# OSSIDevBoard.net
KiCad netlist of a schematic drawn in EAGLE
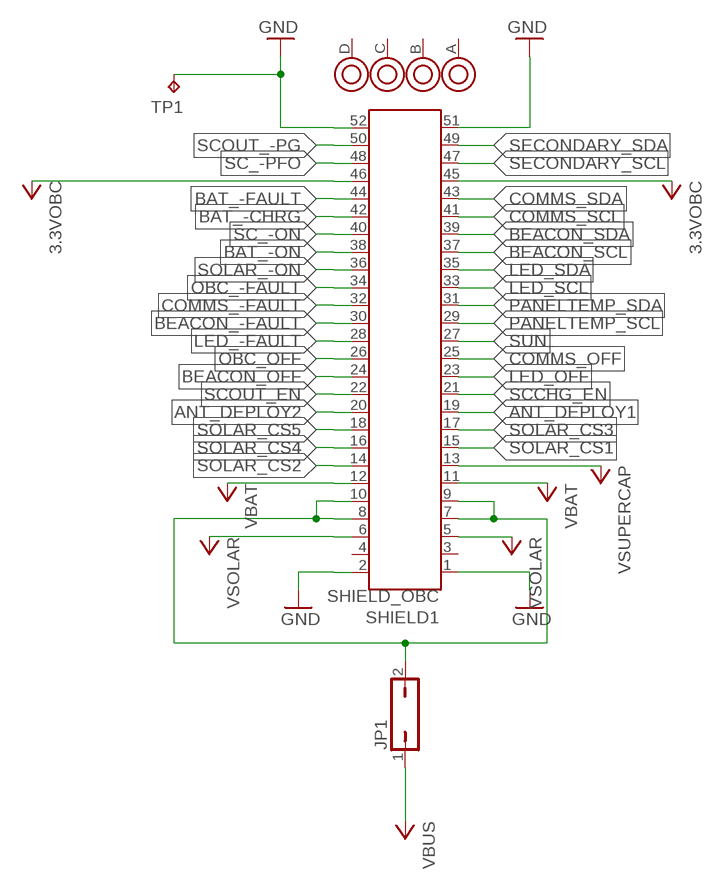
[diagram p0: schematic, sheet 1, part 1 of 2]
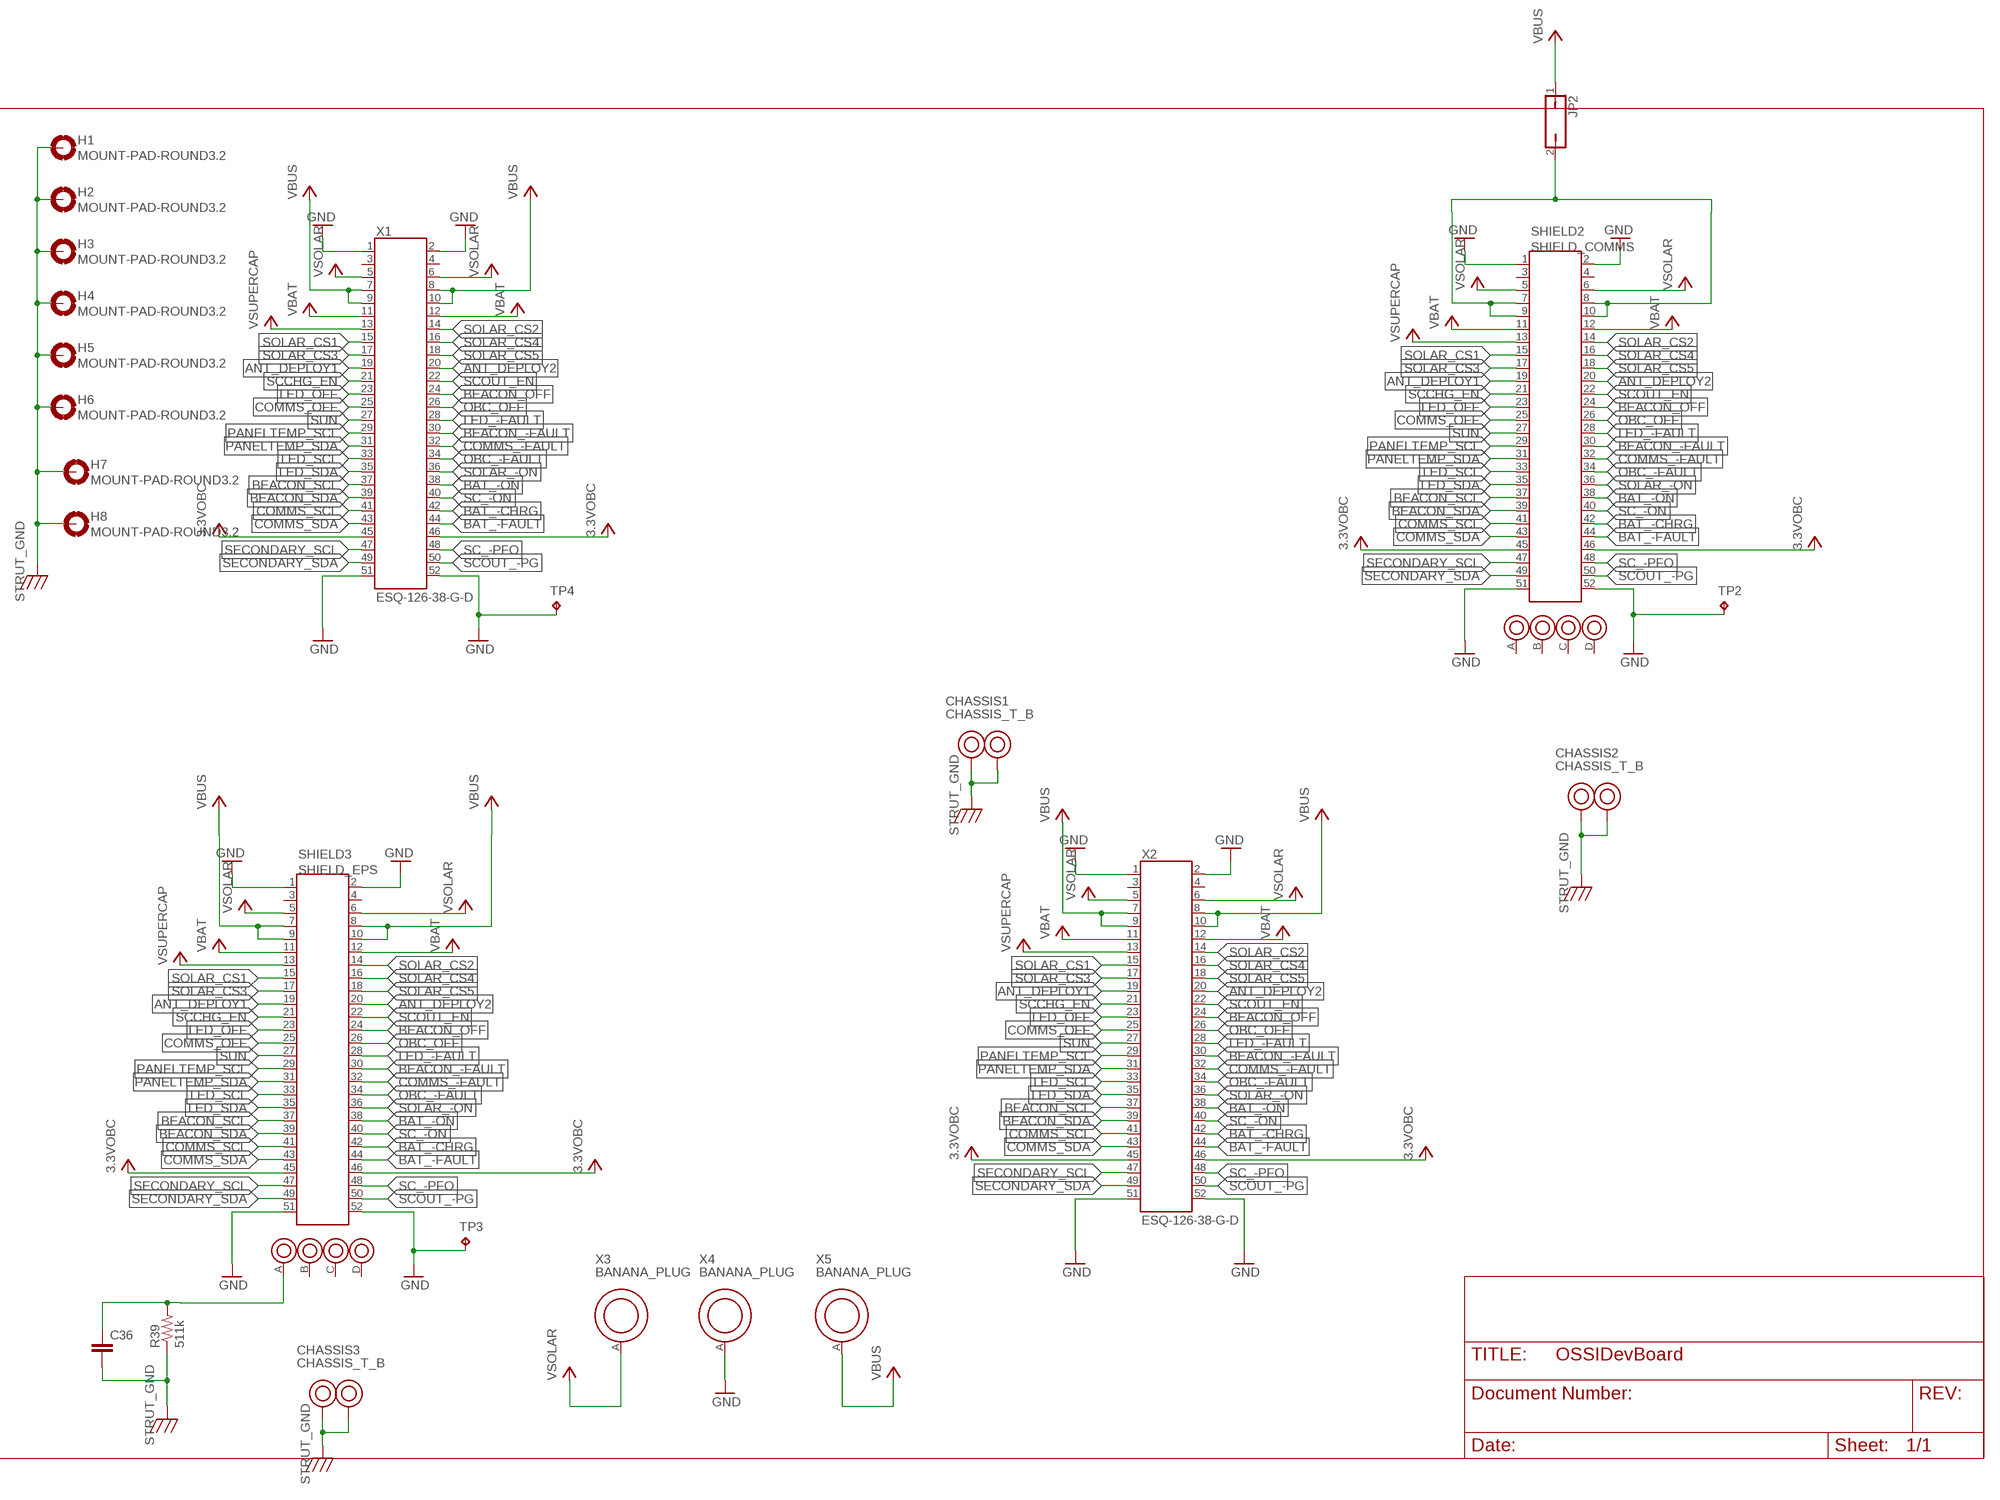
[diagram p1: schematic, sheet 1, part 2 of 2]

(export (version "E")
  (design (tool "Eeschema 10.0.6"))
  (components
    (comp (ref "C36")
      (value "C0805(2012)")
      (footprint "eagle-import:C0805(2012)")
      (libsource (lib "eagle-import") (part "C0805(2012)"))
    )
    (comp (ref "CHASSIS1")
      (value "CHASSIS_T_B")
      (footprint "eagle-import:CHASSIS_T_B")
      (libsource (lib "eagle-import") (part "CHASSIS_T_B"))
    )
    (comp (ref "CHASSIS2")
      (value "CHASSIS_T_B")
      (footprint "eagle-import:CHASSIS_T_B")
      (libsource (lib "eagle-import") (part "CHASSIS_T_B"))
    )
    (comp (ref "CHASSIS3")
      (value "CHASSIS_T_B")
      (footprint "eagle-import:CHASSIS_T_B")
      (libsource (lib "eagle-import") (part "CHASSIS_T_B"))
    )
    (comp (ref "H1")
      (value "MOUNT-PAD-ROUND3.2")
      (footprint "eagle-import:3.2-PAD-ROUND")
      (libsource (lib "eagle-import") (part "MOUNT-PAD-ROUND3.2"))
    )
    (comp (ref "H2")
      (value "MOUNT-PAD-ROUND3.2")
      (footprint "eagle-import:3.2-PAD-ROUND")
      (libsource (lib "eagle-import") (part "MOUNT-PAD-ROUND3.2"))
    )
    (comp (ref "H3")
      (value "MOUNT-PAD-ROUND3.2")
      (footprint "eagle-import:3.2-PAD-ROUND")
      (libsource (lib "eagle-import") (part "MOUNT-PAD-ROUND3.2"))
    )
    (comp (ref "H4")
      (value "MOUNT-PAD-ROUND3.2")
      (footprint "eagle-import:3.2-PAD-ROUND")
      (libsource (lib "eagle-import") (part "MOUNT-PAD-ROUND3.2"))
    )
    (comp (ref "H5")
      (value "MOUNT-PAD-ROUND3.2")
      (footprint "eagle-import:3.2-PAD-ROUND")
      (libsource (lib "eagle-import") (part "MOUNT-PAD-ROUND3.2"))
    )
    (comp (ref "H6")
      (value "MOUNT-PAD-ROUND3.2")
      (footprint "eagle-import:3.2-PAD-ROUND")
      (libsource (lib "eagle-import") (part "MOUNT-PAD-ROUND3.2"))
    )
    (comp (ref "H7")
      (value "MOUNT-PAD-ROUND3.2")
      (footprint "eagle-import:3.2-PAD-ROUND")
      (libsource (lib "eagle-import") (part "MOUNT-PAD-ROUND3.2"))
    )
    (comp (ref "H8")
      (value "MOUNT-PAD-ROUND3.2")
      (footprint "eagle-import:3.2-PAD-ROUND")
      (libsource (lib "eagle-import") (part "MOUNT-PAD-ROUND3.2"))
    )
    (comp (ref "JP1")
      (value "JP1Q")
      (footprint "eagle-import:JP1")
      (libsource (lib "eagle-import") (part "JP1Q"))
    )
    (comp (ref "JP2")
      (value "JP1Q")
      (footprint "eagle-import:JP1")
      (libsource (lib "eagle-import") (part "JP1Q"))
    )
    (comp (ref "R39")
      (value "511k")
      (footprint "eagle-import:R0805(2012)")
      (libsource (lib "eagle-import") (part "R0805(2012)"))
    )
    (comp (ref "SHIELD1")
      (value "SHIELD_OBC")
      (footprint "eagle-import:OBC_SHIELD")
      (libsource (lib "eagle-import") (part "SHIELD_OBC"))
    )
    (comp (ref "SHIELD2")
      (value "SHIELD_COMMS")
      (footprint "eagle-import:COMMS_SHIELD")
      (libsource (lib "eagle-import") (part "SHIELD_COMMS"))
    )
    (comp (ref "SHIELD3")
      (value "SHIELD_EPS")
      (footprint "eagle-import:EPS_SHIELD")
      (libsource (lib "eagle-import") (part "SHIELD_EPS"))
    )
    (comp (ref "TP1")
      (value "TP")
      (footprint "eagle-import:TP-13")
      (libsource (lib "eagle-import") (part "TP"))
    )
    (comp (ref "TP2")
      (value "TP")
      (footprint "eagle-import:TP-13")
      (libsource (lib "eagle-import") (part "TP"))
    )
    (comp (ref "TP3")
      (value "TP")
      (footprint "eagle-import:TP-13")
      (libsource (lib "eagle-import") (part "TP"))
    )
    (comp (ref "TP4")
      (value "TP")
      (footprint "eagle-import:TP-13")
      (libsource (lib "eagle-import") (part "TP"))
    )
    (comp (ref "X1")
      (value "ESQ-126-38-G-D")
      (footprint "eagle-import:ESQ-126-XX-X-D")
      (libsource (lib "eagle-import") (part "ESQ-126-38-G-D"))
    )
    (comp (ref "X2")
      (value "ESQ-126-38-G-D")
      (footprint "eagle-import:ESQ-126-XX-X-D")
      (libsource (lib "eagle-import") (part "ESQ-126-38-G-D"))
    )
    (comp (ref "X3")
      (value "BANANA_PLUG")
      (footprint "eagle-import:BANANA_PLUG")
      (libsource (lib "eagle-import") (part "BANANA_PLUG"))
    )
    (comp (ref "X4")
      (value "BANANA_PLUG")
      (footprint "eagle-import:BANANA_PLUG")
      (libsource (lib "eagle-import") (part "BANANA_PLUG"))
    )
    (comp (ref "X5")
      (value "BANANA_PLUG")
      (footprint "eagle-import:BANANA_PLUG")
      (libsource (lib "eagle-import") (part "BANANA_PLUG"))
    )
  )
  (nets
    (net (code "1") (name "3.3VOBC") (class "Default")
      (node (ref "SHIELD1") (pin "45") (pinfunction "45_45") (pintype "bidirectional"))
      (node (ref "SHIELD1") (pin "46") (pinfunction "46_46") (pintype "bidirectional"))
      (node (ref "SHIELD2") (pin "45") (pinfunction "45_45") (pintype "bidirectional"))
      (node (ref "SHIELD2") (pin "46") (pinfunction "46_46") (pintype "bidirectional"))
      (node (ref "SHIELD3") (pin "45") (pinfunction "45_45") (pintype "bidirectional"))
      (node (ref "SHIELD3") (pin "46") (pinfunction "46_46") (pintype "bidirectional"))
      (node (ref "X1") (pin "45") (pinfunction "45_45") (pintype "bidirectional"))
      (node (ref "X1") (pin "46") (pinfunction "46_46") (pintype "bidirectional"))
      (node (ref "X2") (pin "45") (pinfunction "45_45") (pintype "bidirectional"))
      (node (ref "X2") (pin "46") (pinfunction "46_46") (pintype "bidirectional"))
    )
    (net (code "2") (name "ANT_DEPLOY1") (class "Default")
      (node (ref "SHIELD1") (pin "19") (pinfunction "19_19") (pintype "bidirectional"))
      (node (ref "SHIELD2") (pin "19") (pinfunction "19_19") (pintype "bidirectional"))
      (node (ref "SHIELD3") (pin "19") (pinfunction "19_19") (pintype "bidirectional"))
      (node (ref "X1") (pin "19") (pinfunction "19_19") (pintype "bidirectional"))
      (node (ref "X2") (pin "19") (pinfunction "19_19") (pintype "bidirectional"))
    )
    (net (code "3") (name "ANT_DEPLOY2") (class "Default")
      (node (ref "SHIELD1") (pin "20") (pinfunction "20_20") (pintype "bidirectional"))
      (node (ref "SHIELD2") (pin "20") (pinfunction "20_20") (pintype "bidirectional"))
      (node (ref "SHIELD3") (pin "20") (pinfunction "20_20") (pintype "bidirectional"))
      (node (ref "X1") (pin "20") (pinfunction "20_20") (pintype "bidirectional"))
      (node (ref "X2") (pin "20") (pinfunction "20_20") (pintype "bidirectional"))
    )
    (net (code "4") (name "BAT_-CHRG") (class "Default")
      (node (ref "SHIELD1") (pin "42") (pinfunction "42_42") (pintype "bidirectional"))
      (node (ref "SHIELD2") (pin "42") (pinfunction "42_42") (pintype "bidirectional"))
      (node (ref "SHIELD3") (pin "42") (pinfunction "42_42") (pintype "bidirectional"))
      (node (ref "X1") (pin "42") (pinfunction "42_42") (pintype "bidirectional"))
      (node (ref "X2") (pin "42") (pinfunction "42_42") (pintype "bidirectional"))
    )
    (net (code "5") (name "BAT_-FAULT") (class "Default")
      (node (ref "SHIELD1") (pin "44") (pinfunction "44_44") (pintype "bidirectional"))
      (node (ref "SHIELD2") (pin "44") (pinfunction "44_44") (pintype "bidirectional"))
      (node (ref "SHIELD3") (pin "44") (pinfunction "44_44") (pintype "bidirectional"))
      (node (ref "X1") (pin "44") (pinfunction "44_44") (pintype "bidirectional"))
      (node (ref "X2") (pin "44") (pinfunction "44_44") (pintype "bidirectional"))
    )
    (net (code "6") (name "BAT_-ON") (class "Default")
      (node (ref "SHIELD1") (pin "38") (pinfunction "38_38") (pintype "bidirectional"))
      (node (ref "SHIELD2") (pin "38") (pinfunction "38_38") (pintype "bidirectional"))
      (node (ref "SHIELD3") (pin "38") (pinfunction "38_38") (pintype "bidirectional"))
      (node (ref "X1") (pin "38") (pinfunction "38_38") (pintype "bidirectional"))
      (node (ref "X2") (pin "38") (pinfunction "38_38") (pintype "bidirectional"))
    )
    (net (code "7") (name "BEACON_-FAULT") (class "Default")
      (node (ref "SHIELD1") (pin "30") (pinfunction "30_30") (pintype "bidirectional"))
      (node (ref "SHIELD2") (pin "30") (pinfunction "30_30") (pintype "bidirectional"))
      (node (ref "SHIELD3") (pin "30") (pinfunction "30_30") (pintype "bidirectional"))
      (node (ref "X1") (pin "30") (pinfunction "30_30") (pintype "bidirectional"))
      (node (ref "X2") (pin "30") (pinfunction "30_30") (pintype "bidirectional"))
    )
    (net (code "8") (name "BEACON_OFF") (class "Default")
      (node (ref "SHIELD1") (pin "24") (pinfunction "24_24") (pintype "bidirectional"))
      (node (ref "SHIELD2") (pin "24") (pinfunction "24_24") (pintype "bidirectional"))
      (node (ref "SHIELD3") (pin "24") (pinfunction "24_24") (pintype "bidirectional"))
      (node (ref "X1") (pin "24") (pinfunction "24_24") (pintype "bidirectional"))
      (node (ref "X2") (pin "24") (pinfunction "24_24") (pintype "bidirectional"))
    )
    (net (code "9") (name "BEACON_SCL") (class "Default")
      (node (ref "SHIELD1") (pin "37") (pinfunction "37_37") (pintype "bidirectional"))
      (node (ref "SHIELD2") (pin "37") (pinfunction "37_37") (pintype "bidirectional"))
      (node (ref "SHIELD3") (pin "37") (pinfunction "37_37") (pintype "bidirectional"))
      (node (ref "X1") (pin "37") (pinfunction "37_37") (pintype "bidirectional"))
      (node (ref "X2") (pin "37") (pinfunction "37_37") (pintype "bidirectional"))
    )
    (net (code "10") (name "BEACON_SDA") (class "Default")
      (node (ref "SHIELD1") (pin "39") (pinfunction "39_39") (pintype "bidirectional"))
      (node (ref "SHIELD2") (pin "39") (pinfunction "39_39") (pintype "bidirectional"))
      (node (ref "SHIELD3") (pin "39") (pinfunction "39_39") (pintype "bidirectional"))
      (node (ref "X1") (pin "39") (pinfunction "39_39") (pintype "bidirectional"))
      (node (ref "X2") (pin "39") (pinfunction "39_39") (pintype "bidirectional"))
    )
    (net (code "11") (name "COMMS_-FAULT") (class "Default")
      (node (ref "SHIELD1") (pin "32") (pinfunction "32_32") (pintype "bidirectional"))
      (node (ref "SHIELD2") (pin "32") (pinfunction "32_32") (pintype "bidirectional"))
      (node (ref "SHIELD3") (pin "32") (pinfunction "32_32") (pintype "bidirectional"))
      (node (ref "X1") (pin "32") (pinfunction "32_32") (pintype "bidirectional"))
      (node (ref "X2") (pin "32") (pinfunction "32_32") (pintype "bidirectional"))
    )
    (net (code "12") (name "COMMS_OFF") (class "Default")
      (node (ref "SHIELD1") (pin "25") (pinfunction "25_25") (pintype "bidirectional"))
      (node (ref "SHIELD2") (pin "25") (pinfunction "25_25") (pintype "bidirectional"))
      (node (ref "SHIELD3") (pin "25") (pinfunction "25_25") (pintype "bidirectional"))
      (node (ref "X1") (pin "25") (pinfunction "25_25") (pintype "bidirectional"))
      (node (ref "X2") (pin "25") (pinfunction "25_25") (pintype "bidirectional"))
    )
    (net (code "13") (name "COMMS_SCL") (class "Default")
      (node (ref "SHIELD1") (pin "41") (pinfunction "41_41") (pintype "bidirectional"))
      (node (ref "SHIELD2") (pin "41") (pinfunction "41_41") (pintype "bidirectional"))
      (node (ref "SHIELD3") (pin "41") (pinfunction "41_41") (pintype "bidirectional"))
      (node (ref "X1") (pin "41") (pinfunction "41_41") (pintype "bidirectional"))
      (node (ref "X2") (pin "41") (pinfunction "41_41") (pintype "bidirectional"))
    )
    (net (code "14") (name "COMMS_SDA") (class "Default")
      (node (ref "SHIELD1") (pin "43") (pinfunction "43_43") (pintype "bidirectional"))
      (node (ref "SHIELD2") (pin "43") (pinfunction "43_43") (pintype "bidirectional"))
      (node (ref "SHIELD3") (pin "43") (pinfunction "43_43") (pintype "bidirectional"))
      (node (ref "X1") (pin "43") (pinfunction "43_43") (pintype "bidirectional"))
      (node (ref "X2") (pin "43") (pinfunction "43_43") (pintype "bidirectional"))
    )
    (net (code "15") (name "GND") (class "Default")
      (node (ref "SHIELD1") (pin "1") (pinfunction "1_1") (pintype "bidirectional"))
      (node (ref "SHIELD1") (pin "2") (pinfunction "2_2") (pintype "bidirectional"))
      (node (ref "SHIELD1") (pin "51") (pinfunction "51_51") (pintype "bidirectional"))
      (node (ref "SHIELD1") (pin "52") (pinfunction "52_52") (pintype "bidirectional"))
      (node (ref "SHIELD2") (pin "1") (pinfunction "1_1") (pintype "bidirectional"))
      (node (ref "SHIELD2") (pin "2") (pinfunction "2_2") (pintype "bidirectional"))
      (node (ref "SHIELD2") (pin "51") (pinfunction "51_51") (pintype "bidirectional"))
      (node (ref "SHIELD2") (pin "52") (pinfunction "52_52") (pintype "bidirectional"))
      (node (ref "SHIELD3") (pin "1") (pinfunction "1_1") (pintype "bidirectional"))
      (node (ref "SHIELD3") (pin "2") (pinfunction "2_2") (pintype "bidirectional"))
      (node (ref "SHIELD3") (pin "51") (pinfunction "51_51") (pintype "bidirectional"))
      (node (ref "SHIELD3") (pin "52") (pinfunction "52_52") (pintype "bidirectional"))
      (node (ref "TP1") (pin "TP") (pinfunction "TP_TP") (pintype "input"))
      (node (ref "TP2") (pin "TP") (pinfunction "TP_TP") (pintype "input"))
      (node (ref "TP3") (pin "TP") (pinfunction "TP_TP") (pintype "input"))
      (node (ref "TP4") (pin "TP") (pinfunction "TP_TP") (pintype "input"))
      (node (ref "X1") (pin "1") (pinfunction "1_1") (pintype "bidirectional"))
      (node (ref "X1") (pin "2") (pinfunction "2_2") (pintype "bidirectional"))
      (node (ref "X1") (pin "51") (pinfunction "51_51") (pintype "bidirectional"))
      (node (ref "X1") (pin "52") (pinfunction "52_52") (pintype "bidirectional"))
      (node (ref "X2") (pin "1") (pinfunction "1_1") (pintype "bidirectional"))
      (node (ref "X2") (pin "2") (pinfunction "2_2") (pintype "bidirectional"))
      (node (ref "X2") (pin "51") (pinfunction "51_51") (pintype "bidirectional"))
      (node (ref "X2") (pin "52") (pinfunction "52_52") (pintype "bidirectional"))
      (node (ref "X4") (pin "A") (pinfunction "A_A") (pintype "bidirectional"))
    )
    (net (code "16") (name "LED_-FAULT") (class "Default")
      (node (ref "SHIELD1") (pin "28") (pinfunction "28_28") (pintype "bidirectional"))
      (node (ref "SHIELD2") (pin "28") (pinfunction "28_28") (pintype "bidirectional"))
      (node (ref "SHIELD3") (pin "28") (pinfunction "28_28") (pintype "bidirectional"))
      (node (ref "X1") (pin "28") (pinfunction "28_28") (pintype "bidirectional"))
      (node (ref "X2") (pin "28") (pinfunction "28_28") (pintype "bidirectional"))
    )
    (net (code "17") (name "LED_OFF") (class "Default")
      (node (ref "SHIELD1") (pin "23") (pinfunction "23_23") (pintype "bidirectional"))
      (node (ref "SHIELD2") (pin "23") (pinfunction "23_23") (pintype "bidirectional"))
      (node (ref "SHIELD3") (pin "23") (pinfunction "23_23") (pintype "bidirectional"))
      (node (ref "X1") (pin "23") (pinfunction "23_23") (pintype "bidirectional"))
      (node (ref "X2") (pin "23") (pinfunction "23_23") (pintype "bidirectional"))
    )
    (net (code "18") (name "LED_SCL") (class "Default")
      (node (ref "SHIELD1") (pin "33") (pinfunction "33_33") (pintype "bidirectional"))
      (node (ref "SHIELD2") (pin "33") (pinfunction "33_33") (pintype "bidirectional"))
      (node (ref "SHIELD3") (pin "33") (pinfunction "33_33") (pintype "bidirectional"))
      (node (ref "X1") (pin "33") (pinfunction "33_33") (pintype "bidirectional"))
      (node (ref "X2") (pin "33") (pinfunction "33_33") (pintype "bidirectional"))
    )
    (net (code "19") (name "LED_SDA") (class "Default")
      (node (ref "SHIELD1") (pin "35") (pinfunction "35_35") (pintype "bidirectional"))
      (node (ref "SHIELD2") (pin "35") (pinfunction "35_35") (pintype "bidirectional"))
      (node (ref "SHIELD3") (pin "35") (pinfunction "35_35") (pintype "bidirectional"))
      (node (ref "X1") (pin "35") (pinfunction "35_35") (pintype "bidirectional"))
      (node (ref "X2") (pin "35") (pinfunction "35_35") (pintype "bidirectional"))
    )
    (net (code "20") (name "Net-(C36-Pad1)") (class "Default")
      (node (ref "C36") (pin "1") (pinfunction "1_1") (pintype "passive"))
      (node (ref "R39") (pin "2") (pinfunction "2_2") (pintype "passive"))
      (node (ref "SHIELD3") (pin "A") (pinfunction "A_A") (pintype "bidirectional"))
    )
    (net (code "21") (name "Net-(JP1-Pad2)") (class "Default")
      (node (ref "JP1") (pin "2") (pinfunction "2_2") (pintype "passive"))
      (node (ref "SHIELD1") (pin "10") (pinfunction "10_10") (pintype "bidirectional"))
      (node (ref "SHIELD1") (pin "7") (pinfunction "7_7") (pintype "bidirectional"))
      (node (ref "SHIELD1") (pin "8") (pinfunction "8_8") (pintype "bidirectional"))
      (node (ref "SHIELD1") (pin "9") (pinfunction "9_9") (pintype "bidirectional"))
    )
    (net (code "22") (name "Net-(JP2-Pad2)") (class "Default")
      (node (ref "JP2") (pin "2") (pinfunction "2_2") (pintype "passive"))
      (node (ref "SHIELD2") (pin "10") (pinfunction "10_10") (pintype "bidirectional"))
      (node (ref "SHIELD2") (pin "7") (pinfunction "7_7") (pintype "bidirectional"))
      (node (ref "SHIELD2") (pin "8") (pinfunction "8_8") (pintype "bidirectional"))
      (node (ref "SHIELD2") (pin "9") (pinfunction "9_9") (pintype "bidirectional"))
    )
    (net (code "23") (name "OBC_-FAULT") (class "Default")
      (node (ref "SHIELD1") (pin "34") (pinfunction "34_34") (pintype "bidirectional"))
      (node (ref "SHIELD2") (pin "34") (pinfunction "34_34") (pintype "bidirectional"))
      (node (ref "SHIELD3") (pin "34") (pinfunction "34_34") (pintype "bidirectional"))
      (node (ref "X1") (pin "34") (pinfunction "34_34") (pintype "bidirectional"))
      (node (ref "X2") (pin "34") (pinfunction "34_34") (pintype "bidirectional"))
    )
    (net (code "24") (name "OBC_OFF") (class "Default")
      (node (ref "SHIELD1") (pin "26") (pinfunction "26_26") (pintype "bidirectional"))
      (node (ref "SHIELD2") (pin "26") (pinfunction "26_26") (pintype "bidirectional"))
      (node (ref "SHIELD3") (pin "26") (pinfunction "26_26") (pintype "bidirectional"))
      (node (ref "X1") (pin "26") (pinfunction "26_26") (pintype "bidirectional"))
      (node (ref "X2") (pin "26") (pinfunction "26_26") (pintype "bidirectional"))
    )
    (net (code "25") (name "PANELTEMP_SCL") (class "Default")
      (node (ref "SHIELD1") (pin "29") (pinfunction "29_29") (pintype "bidirectional"))
      (node (ref "SHIELD2") (pin "29") (pinfunction "29_29") (pintype "bidirectional"))
      (node (ref "SHIELD3") (pin "29") (pinfunction "29_29") (pintype "bidirectional"))
      (node (ref "X1") (pin "29") (pinfunction "29_29") (pintype "bidirectional"))
      (node (ref "X2") (pin "29") (pinfunction "29_29") (pintype "bidirectional"))
    )
    (net (code "26") (name "PANELTEMP_SDA") (class "Default")
      (node (ref "SHIELD1") (pin "31") (pinfunction "31_31") (pintype "bidirectional"))
      (node (ref "SHIELD2") (pin "31") (pinfunction "31_31") (pintype "bidirectional"))
      (node (ref "SHIELD3") (pin "31") (pinfunction "31_31") (pintype "bidirectional"))
      (node (ref "X1") (pin "31") (pinfunction "31_31") (pintype "bidirectional"))
      (node (ref "X2") (pin "31") (pinfunction "31_31") (pintype "bidirectional"))
    )
    (net (code "27") (name "SCCHG_EN") (class "Default")
      (node (ref "SHIELD1") (pin "21") (pinfunction "21_21") (pintype "bidirectional"))
      (node (ref "SHIELD2") (pin "21") (pinfunction "21_21") (pintype "bidirectional"))
      (node (ref "SHIELD3") (pin "21") (pinfunction "21_21") (pintype "bidirectional"))
      (node (ref "X1") (pin "21") (pinfunction "21_21") (pintype "bidirectional"))
      (node (ref "X2") (pin "21") (pinfunction "21_21") (pintype "bidirectional"))
    )
    (net (code "28") (name "SCOUT_-PG") (class "Default")
      (node (ref "SHIELD1") (pin "50") (pinfunction "50_50") (pintype "bidirectional"))
      (node (ref "SHIELD2") (pin "50") (pinfunction "50_50") (pintype "bidirectional"))
      (node (ref "SHIELD3") (pin "50") (pinfunction "50_50") (pintype "bidirectional"))
      (node (ref "X1") (pin "50") (pinfunction "50_50") (pintype "bidirectional"))
      (node (ref "X2") (pin "50") (pinfunction "50_50") (pintype "bidirectional"))
    )
    (net (code "29") (name "SCOUT_EN") (class "Default")
      (node (ref "SHIELD1") (pin "22") (pinfunction "22_22") (pintype "bidirectional"))
      (node (ref "SHIELD2") (pin "22") (pinfunction "22_22") (pintype "bidirectional"))
      (node (ref "SHIELD3") (pin "22") (pinfunction "22_22") (pintype "bidirectional"))
      (node (ref "X1") (pin "22") (pinfunction "22_22") (pintype "bidirectional"))
      (node (ref "X2") (pin "22") (pinfunction "22_22") (pintype "bidirectional"))
    )
    (net (code "30") (name "SC_-ON") (class "Default")
      (node (ref "SHIELD1") (pin "40") (pinfunction "40_40") (pintype "bidirectional"))
      (node (ref "SHIELD2") (pin "40") (pinfunction "40_40") (pintype "bidirectional"))
      (node (ref "SHIELD3") (pin "40") (pinfunction "40_40") (pintype "bidirectional"))
      (node (ref "X1") (pin "40") (pinfunction "40_40") (pintype "bidirectional"))
      (node (ref "X2") (pin "40") (pinfunction "40_40") (pintype "bidirectional"))
    )
    (net (code "31") (name "SC_-PFO") (class "Default")
      (node (ref "SHIELD1") (pin "48") (pinfunction "48_48") (pintype "bidirectional"))
      (node (ref "SHIELD2") (pin "48") (pinfunction "48_48") (pintype "bidirectional"))
      (node (ref "SHIELD3") (pin "48") (pinfunction "48_48") (pintype "bidirectional"))
      (node (ref "X1") (pin "48") (pinfunction "48_48") (pintype "bidirectional"))
      (node (ref "X2") (pin "48") (pinfunction "48_48") (pintype "bidirectional"))
    )
    (net (code "32") (name "SECONDARY_SCL") (class "Default")
      (node (ref "SHIELD1") (pin "47") (pinfunction "47_47") (pintype "bidirectional"))
      (node (ref "SHIELD2") (pin "47") (pinfunction "47_47") (pintype "bidirectional"))
      (node (ref "SHIELD3") (pin "47") (pinfunction "47_47") (pintype "bidirectional"))
      (node (ref "X1") (pin "47") (pinfunction "47_47") (pintype "bidirectional"))
      (node (ref "X2") (pin "47") (pinfunction "47_47") (pintype "bidirectional"))
    )
    (net (code "33") (name "SECONDARY_SDA") (class "Default")
      (node (ref "SHIELD1") (pin "49") (pinfunction "49_49") (pintype "bidirectional"))
      (node (ref "SHIELD2") (pin "49") (pinfunction "49_49") (pintype "bidirectional"))
      (node (ref "SHIELD3") (pin "49") (pinfunction "49_49") (pintype "bidirectional"))
      (node (ref "X1") (pin "49") (pinfunction "49_49") (pintype "bidirectional"))
      (node (ref "X2") (pin "49") (pinfunction "49_49") (pintype "bidirectional"))
    )
    (net (code "34") (name "SOLAR_-ON") (class "Default")
      (node (ref "SHIELD1") (pin "36") (pinfunction "36_36") (pintype "bidirectional"))
      (node (ref "SHIELD2") (pin "36") (pinfunction "36_36") (pintype "bidirectional"))
      (node (ref "SHIELD3") (pin "36") (pinfunction "36_36") (pintype "bidirectional"))
      (node (ref "X1") (pin "36") (pinfunction "36_36") (pintype "bidirectional"))
      (node (ref "X2") (pin "36") (pinfunction "36_36") (pintype "bidirectional"))
    )
    (net (code "35") (name "SOLAR_CS1") (class "Default")
      (node (ref "SHIELD1") (pin "15") (pinfunction "15_15") (pintype "bidirectional"))
      (node (ref "SHIELD2") (pin "15") (pinfunction "15_15") (pintype "bidirectional"))
      (node (ref "SHIELD3") (pin "15") (pinfunction "15_15") (pintype "bidirectional"))
      (node (ref "X1") (pin "15") (pinfunction "15_15") (pintype "bidirectional"))
      (node (ref "X2") (pin "15") (pinfunction "15_15") (pintype "bidirectional"))
    )
    (net (code "36") (name "SOLAR_CS2") (class "Default")
      (node (ref "SHIELD1") (pin "14") (pinfunction "14_14") (pintype "bidirectional"))
      (node (ref "SHIELD2") (pin "14") (pinfunction "14_14") (pintype "bidirectional"))
      (node (ref "SHIELD3") (pin "14") (pinfunction "14_14") (pintype "bidirectional"))
      (node (ref "X1") (pin "14") (pinfunction "14_14") (pintype "bidirectional"))
      (node (ref "X2") (pin "14") (pinfunction "14_14") (pintype "bidirectional"))
    )
    (net (code "37") (name "SOLAR_CS3") (class "Default")
      (node (ref "SHIELD1") (pin "17") (pinfunction "17_17") (pintype "bidirectional"))
      (node (ref "SHIELD2") (pin "17") (pinfunction "17_17") (pintype "bidirectional"))
      (node (ref "SHIELD3") (pin "17") (pinfunction "17_17") (pintype "bidirectional"))
      (node (ref "X1") (pin "17") (pinfunction "17_17") (pintype "bidirectional"))
      (node (ref "X2") (pin "17") (pinfunction "17_17") (pintype "bidirectional"))
    )
    (net (code "38") (name "SOLAR_CS4") (class "Default")
      (node (ref "SHIELD1") (pin "16") (pinfunction "16_16") (pintype "bidirectional"))
      (node (ref "SHIELD2") (pin "16") (pinfunction "16_16") (pintype "bidirectional"))
      (node (ref "SHIELD3") (pin "16") (pinfunction "16_16") (pintype "bidirectional"))
      (node (ref "X1") (pin "16") (pinfunction "16_16") (pintype "bidirectional"))
      (node (ref "X2") (pin "16") (pinfunction "16_16") (pintype "bidirectional"))
    )
    (net (code "39") (name "SOLAR_CS5") (class "Default")
      (node (ref "SHIELD1") (pin "18") (pinfunction "18_18") (pintype "bidirectional"))
      (node (ref "SHIELD2") (pin "18") (pinfunction "18_18") (pintype "bidirectional"))
      (node (ref "SHIELD3") (pin "18") (pinfunction "18_18") (pintype "bidirectional"))
      (node (ref "X1") (pin "18") (pinfunction "18_18") (pintype "bidirectional"))
      (node (ref "X2") (pin "18") (pinfunction "18_18") (pintype "bidirectional"))
    )
    (net (code "40") (name "STRUT_GND") (class "Default")
      (node (ref "C36") (pin "2") (pinfunction "2_2") (pintype "passive"))
      (node (ref "CHASSIS1") (pin "A") (pinfunction "A_A") (pintype "bidirectional"))
      (node (ref "CHASSIS1") (pin "B") (pinfunction "B_B") (pintype "bidirectional"))
      (node (ref "CHASSIS2") (pin "A") (pinfunction "A_A") (pintype "bidirectional"))
      (node (ref "CHASSIS2") (pin "B") (pinfunction "B_B") (pintype "bidirectional"))
      (node (ref "CHASSIS3") (pin "A") (pinfunction "A_A") (pintype "bidirectional"))
      (node (ref "CHASSIS3") (pin "B") (pinfunction "B_B") (pintype "bidirectional"))
      (node (ref "H1") (pin "B3,2") (pinfunction "MOUNT_B3,2") (pintype "passive"))
      (node (ref "H2") (pin "B3,2") (pinfunction "MOUNT_B3,2") (pintype "passive"))
      (node (ref "H3") (pin "B3,2") (pinfunction "MOUNT_B3,2") (pintype "passive"))
      (node (ref "H4") (pin "B3,2") (pinfunction "MOUNT_B3,2") (pintype "passive"))
      (node (ref "H5") (pin "B3,2") (pinfunction "MOUNT_B3,2") (pintype "passive"))
      (node (ref "H6") (pin "B3,2") (pinfunction "MOUNT_B3,2") (pintype "passive"))
      (node (ref "H7") (pin "B3,2") (pinfunction "MOUNT_B3,2") (pintype "passive"))
      (node (ref "H8") (pin "B3,2") (pinfunction "MOUNT_B3,2") (pintype "passive"))
      (node (ref "R39") (pin "1") (pinfunction "1_1") (pintype "passive"))
    )
    (net (code "41") (name "SUN") (class "Default")
      (node (ref "SHIELD1") (pin "27") (pinfunction "27_27") (pintype "bidirectional"))
      (node (ref "SHIELD2") (pin "27") (pinfunction "27_27") (pintype "bidirectional"))
      (node (ref "SHIELD3") (pin "27") (pinfunction "27_27") (pintype "bidirectional"))
      (node (ref "X1") (pin "27") (pinfunction "27_27") (pintype "bidirectional"))
      (node (ref "X2") (pin "27") (pinfunction "27_27") (pintype "bidirectional"))
    )
    (net (code "42") (name "VBAT") (class "Default")
      (node (ref "SHIELD1") (pin "11") (pinfunction "11_11") (pintype "bidirectional"))
      (node (ref "SHIELD1") (pin "12") (pinfunction "12_12") (pintype "bidirectional"))
      (node (ref "SHIELD2") (pin "11") (pinfunction "11_11") (pintype "bidirectional"))
      (node (ref "SHIELD2") (pin "12") (pinfunction "12_12") (pintype "bidirectional"))
      (node (ref "SHIELD3") (pin "11") (pinfunction "11_11") (pintype "bidirectional"))
      (node (ref "SHIELD3") (pin "12") (pinfunction "12_12") (pintype "bidirectional"))
      (node (ref "X1") (pin "11") (pinfunction "11_11") (pintype "bidirectional"))
      (node (ref "X1") (pin "12") (pinfunction "12_12") (pintype "bidirectional"))
      (node (ref "X2") (pin "11") (pinfunction "11_11") (pintype "bidirectional"))
      (node (ref "X2") (pin "12") (pinfunction "12_12") (pintype "bidirectional"))
    )
    (net (code "43") (name "VBUS") (class "Default")
      (node (ref "JP1") (pin "1") (pinfunction "1_1") (pintype "passive"))
      (node (ref "JP2") (pin "1") (pinfunction "1_1") (pintype "passive"))
      (node (ref "SHIELD3") (pin "10") (pinfunction "10_10") (pintype "bidirectional"))
      (node (ref "SHIELD3") (pin "7") (pinfunction "7_7") (pintype "bidirectional"))
      (node (ref "SHIELD3") (pin "8") (pinfunction "8_8") (pintype "bidirectional"))
      (node (ref "SHIELD3") (pin "9") (pinfunction "9_9") (pintype "bidirectional"))
      (node (ref "X1") (pin "10") (pinfunction "10_10") (pintype "bidirectional"))
      (node (ref "X1") (pin "7") (pinfunction "7_7") (pintype "bidirectional"))
      (node (ref "X1") (pin "8") (pinfunction "8_8") (pintype "bidirectional"))
      (node (ref "X1") (pin "9") (pinfunction "9_9") (pintype "bidirectional"))
      (node (ref "X2") (pin "10") (pinfunction "10_10") (pintype "bidirectional"))
      (node (ref "X2") (pin "7") (pinfunction "7_7") (pintype "bidirectional"))
      (node (ref "X2") (pin "8") (pinfunction "8_8") (pintype "bidirectional"))
      (node (ref "X2") (pin "9") (pinfunction "9_9") (pintype "bidirectional"))
      (node (ref "X5") (pin "A") (pinfunction "A_A") (pintype "bidirectional"))
    )
    (net (code "44") (name "VSOLAR") (class "Default")
      (node (ref "SHIELD1") (pin "5") (pinfunction "5_5") (pintype "bidirectional"))
      (node (ref "SHIELD1") (pin "6") (pinfunction "6_6") (pintype "bidirectional"))
      (node (ref "SHIELD2") (pin "5") (pinfunction "5_5") (pintype "bidirectional"))
      (node (ref "SHIELD2") (pin "6") (pinfunction "6_6") (pintype "bidirectional"))
      (node (ref "SHIELD3") (pin "5") (pinfunction "5_5") (pintype "bidirectional"))
      (node (ref "SHIELD3") (pin "6") (pinfunction "6_6") (pintype "bidirectional"))
      (node (ref "X1") (pin "5") (pinfunction "5_5") (pintype "bidirectional"))
      (node (ref "X1") (pin "6") (pinfunction "6_6") (pintype "bidirectional"))
      (node (ref "X2") (pin "5") (pinfunction "5_5") (pintype "bidirectional"))
      (node (ref "X2") (pin "6") (pinfunction "6_6") (pintype "bidirectional"))
      (node (ref "X3") (pin "A") (pinfunction "A_A") (pintype "bidirectional"))
    )
    (net (code "45") (name "VSUPERCAP") (class "Default")
      (node (ref "SHIELD1") (pin "13") (pinfunction "13_13") (pintype "bidirectional"))
      (node (ref "SHIELD2") (pin "13") (pinfunction "13_13") (pintype "bidirectional"))
      (node (ref "SHIELD3") (pin "13") (pinfunction "13_13") (pintype "bidirectional"))
      (node (ref "X1") (pin "13") (pinfunction "13_13") (pintype "bidirectional"))
      (node (ref "X2") (pin "13") (pinfunction "13_13") (pintype "bidirectional"))
    )
    (net (code "46") (name "unconnected-(SHIELD1-Pad3)") (class "Default")
      (node (ref "SHIELD1") (pin "3") (pinfunction "3_3") (pintype "bidirectional"))
    )
    (net (code "47") (name "unconnected-(SHIELD1-Pad4)") (class "Default")
      (node (ref "SHIELD1") (pin "4") (pinfunction "4_4") (pintype "bidirectional"))
    )
    (net (code "48") (name "unconnected-(SHIELD1-PadA)") (class "Default")
      (node (ref "SHIELD1") (pin "A") (pinfunction "A_A") (pintype "bidirectional"))
    )
    (net (code "49") (name "unconnected-(SHIELD1-PadB)") (class "Default")
      (node (ref "SHIELD1") (pin "B") (pinfunction "B_B") (pintype "bidirectional"))
    )
    (net (code "50") (name "unconnected-(SHIELD1-PadC)") (class "Default")
      (node (ref "SHIELD1") (pin "C") (pinfunction "C_C") (pintype "bidirectional"))
    )
    (net (code "51") (name "unconnected-(SHIELD1-PadD)") (class "Default")
      (node (ref "SHIELD1") (pin "D") (pinfunction "D_D") (pintype "bidirectional"))
    )
    (net (code "52") (name "unconnected-(SHIELD2-Pad3)") (class "Default")
      (node (ref "SHIELD2") (pin "3") (pinfunction "3_3") (pintype "bidirectional"))
    )
    (net (code "53") (name "unconnected-(SHIELD2-Pad4)") (class "Default")
      (node (ref "SHIELD2") (pin "4") (pinfunction "4_4") (pintype "bidirectional"))
    )
    (net (code "54") (name "unconnected-(SHIELD2-PadA)") (class "Default")
      (node (ref "SHIELD2") (pin "A") (pinfunction "A_A") (pintype "bidirectional"))
    )
    (net (code "55") (name "unconnected-(SHIELD2-PadB)") (class "Default")
      (node (ref "SHIELD2") (pin "B") (pinfunction "B_B") (pintype "bidirectional"))
    )
    (net (code "56") (name "unconnected-(SHIELD2-PadC)") (class "Default")
      (node (ref "SHIELD2") (pin "C") (pinfunction "C_C") (pintype "bidirectional"))
    )
    (net (code "57") (name "unconnected-(SHIELD2-PadD)") (class "Default")
      (node (ref "SHIELD2") (pin "D") (pinfunction "D_D") (pintype "bidirectional"))
    )
    (net (code "58") (name "unconnected-(SHIELD3-Pad3)") (class "Default")
      (node (ref "SHIELD3") (pin "3") (pinfunction "3_3") (pintype "bidirectional"))
    )
    (net (code "59") (name "unconnected-(SHIELD3-Pad4)") (class "Default")
      (node (ref "SHIELD3") (pin "4") (pinfunction "4_4") (pintype "bidirectional"))
    )
    (net (code "60") (name "unconnected-(SHIELD3-PadB)") (class "Default")
      (node (ref "SHIELD3") (pin "B") (pinfunction "B_B") (pintype "bidirectional"))
    )
    (net (code "61") (name "unconnected-(SHIELD3-PadC)") (class "Default")
      (node (ref "SHIELD3") (pin "C") (pinfunction "C_C") (pintype "bidirectional"))
    )
    (net (code "62") (name "unconnected-(SHIELD3-PadD)") (class "Default")
      (node (ref "SHIELD3") (pin "D") (pinfunction "D_D") (pintype "bidirectional"))
    )
    (net (code "63") (name "unconnected-(X1-Pad3)") (class "Default")
      (node (ref "X1") (pin "3") (pinfunction "3_3") (pintype "bidirectional"))
    )
    (net (code "64") (name "unconnected-(X1-Pad4)") (class "Default")
      (node (ref "X1") (pin "4") (pinfunction "4_4") (pintype "bidirectional"))
    )
    (net (code "65") (name "unconnected-(X2-Pad3)") (class "Default")
      (node (ref "X2") (pin "3") (pinfunction "3_3") (pintype "bidirectional"))
    )
    (net (code "66") (name "unconnected-(X2-Pad4)") (class "Default")
      (node (ref "X2") (pin "4") (pinfunction "4_4") (pintype "bidirectional"))
    )
  )
)
